# cap_pcb.net
KiCad netlist of a schematic drawn in EAGLE
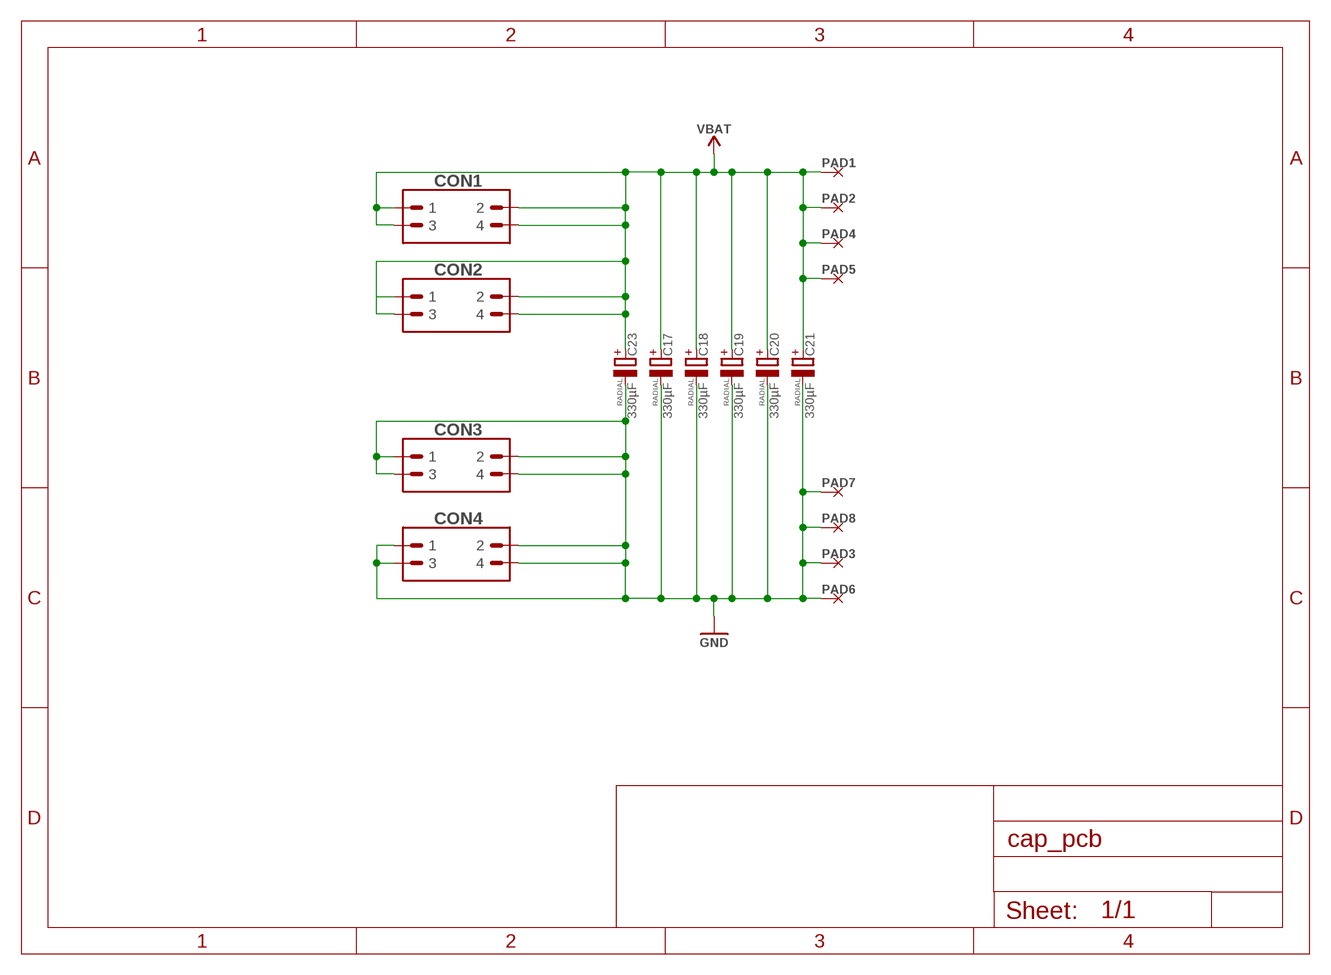
[diagram p0: schematic, sheet 1]

(export (version "E")
  (design (tool "Eeschema 10.0.6"))
  (components
    (comp (ref "C17")
      (value "330µF")
      (footprint "eagle-import:RADIAL_SIDE_12.5X22")
      (fields
        (field (name "PACKAGE") "RADIAL")
        (field (name "MANF") "EPCOS (TDK)")
        (field (name "VOLTAGE") "50V")
        (field (name "DIGIKEY#") "493-4784-3-ND")
        (field (name "MANF_1") "Nichicon")
        (field (name "MANF#") "UCY2C101MHD1TO")
        (field (name "VOLTAGE_1") "160V")
      )
      (libsource (lib "eagle-import") (part "CPOL-RADIAL_SIDE-12.5-22"))
    )
    (comp (ref "C18")
      (value "330µF")
      (footprint "eagle-import:RADIAL_SIDE_12.5X22")
      (fields
        (field (name "PACKAGE") "RADIAL")
        (field (name "MANF") "EPCOS (TDK)")
        (field (name "VOLTAGE") "50V")
        (field (name "DIGIKEY#") "493-4784-3-ND")
        (field (name "MANF_1") "Nichicon")
        (field (name "MANF#") "UCY2C101MHD1TO")
        (field (name "VOLTAGE_1") "160V")
      )
      (libsource (lib "eagle-import") (part "CPOL-RADIAL_SIDE-12.5-22"))
    )
    (comp (ref "C19")
      (value "330µF")
      (footprint "eagle-import:RADIAL_SIDE_12.5X22")
      (fields
        (field (name "PACKAGE") "RADIAL")
        (field (name "MANF") "EPCOS (TDK)")
        (field (name "VOLTAGE") "50V")
        (field (name "DIGIKEY#") "493-4784-3-ND")
        (field (name "MANF_1") "Nichicon")
        (field (name "MANF#") "UCY2C101MHD1TO")
        (field (name "VOLTAGE_1") "160V")
      )
      (libsource (lib "eagle-import") (part "CPOL-RADIAL_SIDE-12.5-22"))
    )
    (comp (ref "C20")
      (value "330µF")
      (footprint "eagle-import:RADIAL_SIDE_12.5X22")
      (fields
        (field (name "PACKAGE") "RADIAL")
        (field (name "MANF") "EPCOS (TDK)")
        (field (name "VOLTAGE") "50V")
        (field (name "DIGIKEY#") "493-4784-3-ND")
        (field (name "MANF_1") "Nichicon")
        (field (name "MANF#") "UCY2C101MHD1TO")
        (field (name "VOLTAGE_1") "160V")
      )
      (libsource (lib "eagle-import") (part "CPOL-RADIAL_SIDE-12.5-22"))
    )
    (comp (ref "C21")
      (value "330µF")
      (footprint "eagle-import:RADIAL_SIDE_12.5X22")
      (fields
        (field (name "PACKAGE") "RADIAL")
        (field (name "MANF") "EPCOS (TDK)")
        (field (name "VOLTAGE") "50V")
        (field (name "DIGIKEY#") "493-4784-3-ND")
        (field (name "MANF_1") "Nichicon")
        (field (name "MANF#") "UCY2C101MHD1TO")
        (field (name "VOLTAGE_1") "160V")
      )
      (libsource (lib "eagle-import") (part "CPOL-RADIAL_SIDE-12.5-22"))
    )
    (comp (ref "C23")
      (value "330µF")
      (footprint "eagle-import:RADIAL_SIDE_12.5X22")
      (fields
        (field (name "PACKAGE") "RADIAL")
        (field (name "MANF") "EPCOS (TDK)")
        (field (name "VOLTAGE") "50V")
        (field (name "DIGIKEY#") "493-4784-3-ND")
        (field (name "MANF_1") "Nichicon")
        (field (name "MANF#") "UCY2C101MHD1TO")
        (field (name "VOLTAGE_1") "160V")
      )
      (libsource (lib "eagle-import") (part "CPOL-RADIAL_SIDE-12.5-22"))
    )
    (comp (ref "CON1")
      (value "PINHEAD_2X02-PTH-2.54-MALE")
      (footprint "eagle-import:2X02-PTH-2.54")
      (libsource (lib "eagle-import") (part "PINHEAD_2X02-PTH-2.54-MALE"))
    )
    (comp (ref "CON2")
      (value "PINHEAD_2X02-PTH-2.54-MALE")
      (footprint "eagle-import:2X02-PTH-2.54")
      (libsource (lib "eagle-import") (part "PINHEAD_2X02-PTH-2.54-MALE"))
    )
    (comp (ref "CON3")
      (value "PINHEAD_2X02-PTH-2.54-MALE")
      (footprint "eagle-import:2X02-PTH-2.54")
      (libsource (lib "eagle-import") (part "PINHEAD_2X02-PTH-2.54-MALE"))
    )
    (comp (ref "CON4")
      (value "PINHEAD_2X02-PTH-2.54-MALE")
      (footprint "eagle-import:2X02-PTH-2.54")
      (libsource (lib "eagle-import") (part "PINHEAD_2X02-PTH-2.54-MALE"))
    )
    (comp (ref "PAD1")
      (value "PAD-5X4")
      (footprint "eagle-import:5X4")
      (libsource (lib "eagle-import") (part "PAD-5X4"))
    )
    (comp (ref "PAD2")
      (value "PAD-5X4")
      (footprint "eagle-import:5X4")
      (libsource (lib "eagle-import") (part "PAD-5X4"))
    )
    (comp (ref "PAD3")
      (value "PAD-5X4")
      (footprint "eagle-import:5X4")
      (libsource (lib "eagle-import") (part "PAD-5X4"))
    )
    (comp (ref "PAD4")
      (value "PAD-5X4")
      (footprint "eagle-import:5X4")
      (libsource (lib "eagle-import") (part "PAD-5X4"))
    )
    (comp (ref "PAD5")
      (value "PAD-5X4")
      (footprint "eagle-import:5X4")
      (libsource (lib "eagle-import") (part "PAD-5X4"))
    )
    (comp (ref "PAD6")
      (value "PAD-5X4")
      (footprint "eagle-import:5X4")
      (libsource (lib "eagle-import") (part "PAD-5X4"))
    )
    (comp (ref "PAD7")
      (value "PAD-5X4")
      (footprint "eagle-import:5X4")
      (libsource (lib "eagle-import") (part "PAD-5X4"))
    )
    (comp (ref "PAD8")
      (value "PAD-5X4")
      (footprint "eagle-import:5X4")
      (libsource (lib "eagle-import") (part "PAD-5X4"))
    )
  )
  (nets
    (net (code "1") (name "GND") (class "Default")
      (node (ref "C17") (pin "-") (pinfunction "-_-") (pintype "passive"))
      (node (ref "C18") (pin "-") (pinfunction "-_-") (pintype "passive"))
      (node (ref "C19") (pin "-") (pinfunction "-_-") (pintype "passive"))
      (node (ref "C20") (pin "-") (pinfunction "-_-") (pintype "passive"))
      (node (ref "C21") (pin "-") (pinfunction "-_-") (pintype "passive"))
      (node (ref "C23") (pin "-") (pinfunction "-_-") (pintype "passive"))
      (node (ref "CON3") (pin "1") (pinfunction "1_1") (pintype "passive"))
      (node (ref "CON3") (pin "2") (pinfunction "2_2") (pintype "passive"))
      (node (ref "CON3") (pin "3") (pinfunction "3_3") (pintype "passive"))
      (node (ref "CON3") (pin "4") (pinfunction "4_4") (pintype "passive"))
      (node (ref "CON4") (pin "1") (pinfunction "1_1") (pintype "passive"))
      (node (ref "CON4") (pin "2") (pinfunction "2_2") (pintype "passive"))
      (node (ref "CON4") (pin "3") (pinfunction "3_3") (pintype "passive"))
      (node (ref "CON4") (pin "4") (pinfunction "4_4") (pintype "passive"))
      (node (ref "PAD3") (pin "P$1") (pinfunction "P$1_P$1") (pintype "bidirectional"))
      (node (ref "PAD6") (pin "P$1") (pinfunction "P$1_P$1") (pintype "bidirectional"))
      (node (ref "PAD7") (pin "P$1") (pinfunction "P$1_P$1") (pintype "bidirectional"))
      (node (ref "PAD8") (pin "P$1") (pinfunction "P$1_P$1") (pintype "bidirectional"))
    )
    (net (code "2") (name "VBAT") (class "Default")
      (node (ref "C17") (pin "+") (pinfunction "+_+") (pintype "passive"))
      (node (ref "C18") (pin "+") (pinfunction "+_+") (pintype "passive"))
      (node (ref "C19") (pin "+") (pinfunction "+_+") (pintype "passive"))
      (node (ref "C20") (pin "+") (pinfunction "+_+") (pintype "passive"))
      (node (ref "C21") (pin "+") (pinfunction "+_+") (pintype "passive"))
      (node (ref "C23") (pin "+") (pinfunction "+_+") (pintype "passive"))
      (node (ref "CON1") (pin "1") (pinfunction "1_1") (pintype "passive"))
      (node (ref "CON1") (pin "2") (pinfunction "2_2") (pintype "passive"))
      (node (ref "CON1") (pin "3") (pinfunction "3_3") (pintype "passive"))
      (node (ref "CON1") (pin "4") (pinfunction "4_4") (pintype "passive"))
      (node (ref "CON2") (pin "1") (pinfunction "1_1") (pintype "passive"))
      (node (ref "CON2") (pin "2") (pinfunction "2_2") (pintype "passive"))
      (node (ref "CON2") (pin "3") (pinfunction "3_3") (pintype "passive"))
      (node (ref "CON2") (pin "4") (pinfunction "4_4") (pintype "passive"))
      (node (ref "PAD1") (pin "P$1") (pinfunction "P$1_P$1") (pintype "bidirectional"))
      (node (ref "PAD2") (pin "P$1") (pinfunction "P$1_P$1") (pintype "bidirectional"))
      (node (ref "PAD4") (pin "P$1") (pinfunction "P$1_P$1") (pintype "bidirectional"))
      (node (ref "PAD5") (pin "P$1") (pinfunction "P$1_P$1") (pintype "bidirectional"))
    )
  )
)
